# scr_precharge.net
KiCad netlist of a schematic drawn in EAGLE
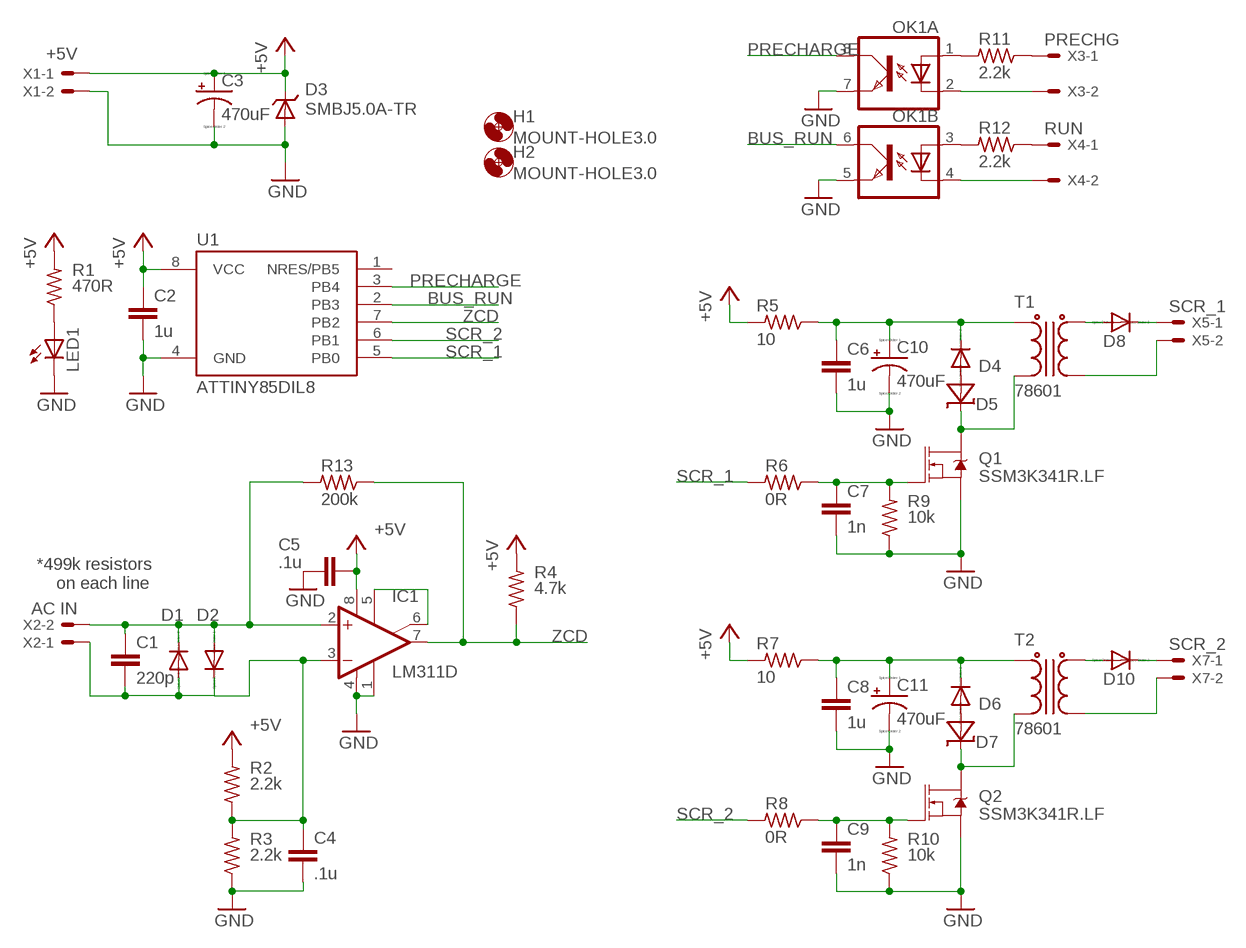
[diagram p0: schematic, sheet 1]

(export (version "E")
  (design (tool "Eeschema 10.0.6"))
  (components
    (comp (ref "C1")
      (value "220p")
      (footprint "eagle-import:C0805")
      (libsource (lib "eagle-import") (part "C-EUC0805"))
    )
    (comp (ref "C2")
      (value "1u")
      (footprint "eagle-import:C0805")
      (libsource (lib "eagle-import") (part "C-EUC0805"))
    )
    (comp (ref "C3")
      (value "470uF")
      (footprint "eagle-import:E3,5-8")
      (libsource (lib "eagle-import") (part "CPOL-USE3.5-8"))
    )
    (comp (ref "C4")
      (value ".1u")
      (footprint "eagle-import:C0805")
      (libsource (lib "eagle-import") (part "C-EUC0805"))
    )
    (comp (ref "C5")
      (value ".1u")
      (footprint "eagle-import:C0805")
      (libsource (lib "eagle-import") (part "C-EUC0805"))
    )
    (comp (ref "C6")
      (value "1u")
      (footprint "eagle-import:C0805")
      (libsource (lib "eagle-import") (part "C-EUC0805"))
    )
    (comp (ref "C7")
      (value "1n")
      (footprint "eagle-import:C0805")
      (libsource (lib "eagle-import") (part "C-EUC0805"))
    )
    (comp (ref "C8")
      (value "1u")
      (footprint "eagle-import:C0805")
      (libsource (lib "eagle-import") (part "C-EUC0805"))
    )
    (comp (ref "C9")
      (value "1n")
      (footprint "eagle-import:C0805")
      (libsource (lib "eagle-import") (part "C-EUC0805"))
    )
    (comp (ref "C10")
      (value "470uF")
      (footprint "eagle-import:E3,5-8")
      (libsource (lib "eagle-import") (part "CPOL-USE3.5-8"))
    )
    (comp (ref "C11")
      (value "470uF")
      (footprint "eagle-import:E3,5-8")
      (libsource (lib "eagle-import") (part "CPOL-USE3.5-8"))
    )
    (comp (ref "D1")
      (value "1N4148MICROMELF")
      (footprint "eagle-import:MICROMELF-W")
      (libsource (lib "eagle-import") (part "1N4148MICROMELF"))
    )
    (comp (ref "D2")
      (value "1N4148MICROMELF")
      (footprint "eagle-import:MICROMELF-W")
      (libsource (lib "eagle-import") (part "1N4148MICROMELF"))
    )
    (comp (ref "D3")
      (value "SMBJ5.0A-TR")
      (footprint "eagle-import:DO214AA")
      (libsource (lib "eagle-import") (part "SMBJ5.0A-TR"))
    )
    (comp (ref "D4")
      (value "1N4148MICROMELF")
      (footprint "eagle-import:MICROMELF-W")
      (libsource (lib "eagle-import") (part "1N4148MICROMELF"))
    )
    (comp (ref "D5")
      (value "SMAZ12-TP")
      (footprint "eagle-import:DO-214AC")
      (libsource (lib "eagle-import") (part "SMAZ12-TP"))
    )
    (comp (ref "D6")
      (value "1N4148MICROMELF")
      (footprint "eagle-import:MICROMELF-W")
      (libsource (lib "eagle-import") (part "1N4148MICROMELF"))
    )
    (comp (ref "D7")
      (value "SMAZ12-TP")
      (footprint "eagle-import:DO-214AC")
      (libsource (lib "eagle-import") (part "SMAZ12-TP"))
    )
    (comp (ref "D8")
      (value "1N4148MICROMELF")
      (footprint "eagle-import:MICROMELF-W")
      (libsource (lib "eagle-import") (part "1N4148MICROMELF"))
    )
    (comp (ref "D10")
      (value "1N4148MICROMELF")
      (footprint "eagle-import:MICROMELF-W")
      (libsource (lib "eagle-import") (part "1N4148MICROMELF"))
    )
    (comp (ref "H1")
      (value "MOUNT-HOLE3.0")
      (footprint "eagle-import:3,0")
      (libsource (lib "eagle-import") (part "MOUNT-HOLE3.0"))
    )
    (comp (ref "H2")
      (value "MOUNT-HOLE3.0")
      (footprint "eagle-import:3,0")
      (libsource (lib "eagle-import") (part "MOUNT-HOLE3.0"))
    )
    (comp (ref "IC1")
      (value "LM311D")
      (footprint "eagle-import:SO08")
      (libsource (lib "eagle-import") (part "LM311D"))
    )
    (comp (ref "LED1")
      (value "LEDCHIP-LED0805")
      (footprint "eagle-import:CHIP-LED0805")
      (libsource (lib "eagle-import") (part "LEDCHIP-LED0805"))
    )
    (comp (ref "OK1")
      (value "ILD621")
      (footprint "eagle-import:DIL08")
      (fields (field (name "MF") "VISHAY/TELEFUNKEN"))
      (libsource (lib "eagle-import") (part "ILD621"))
    )
    (comp (ref "Q1")
      (value "SSM3K341R.LF")
      (footprint "eagle-import:SOT23-3")
      (libsource (lib "eagle-import") (part "MOSFET-NCH-AO3404A"))
    )
    (comp (ref "Q2")
      (value "SSM3K341R.LF")
      (footprint "eagle-import:SOT23-3")
      (libsource (lib "eagle-import") (part "MOSFET-NCH-AO3404A"))
    )
    (comp (ref "R1")
      (value "470R")
      (footprint "eagle-import:R0805")
      (libsource (lib "eagle-import") (part "R-US_R0805"))
    )
    (comp (ref "R2")
      (value "2.2k")
      (footprint "eagle-import:R0805")
      (libsource (lib "eagle-import") (part "R-US_R0805"))
    )
    (comp (ref "R3")
      (value "2.2k")
      (footprint "eagle-import:R0805")
      (libsource (lib "eagle-import") (part "R-US_R0805"))
    )
    (comp (ref "R4")
      (value "4.7k")
      (footprint "eagle-import:R0805")
      (libsource (lib "eagle-import") (part "R-US_R0805"))
    )
    (comp (ref "R5")
      (value "10")
      (footprint "eagle-import:R2010")
      (libsource (lib "eagle-import") (part "R-US_R2010"))
    )
    (comp (ref "R6")
      (value "0R")
      (footprint "eagle-import:R0805")
      (libsource (lib "eagle-import") (part "R-US_R0805"))
    )
    (comp (ref "R7")
      (value "10")
      (footprint "eagle-import:R2010")
      (libsource (lib "eagle-import") (part "R-US_R2010"))
    )
    (comp (ref "R8")
      (value "0R")
      (footprint "eagle-import:R0805")
      (libsource (lib "eagle-import") (part "R-US_R0805"))
    )
    (comp (ref "R9")
      (value "10k")
      (footprint "eagle-import:R0805")
      (libsource (lib "eagle-import") (part "R-US_R0805"))
    )
    (comp (ref "R10")
      (value "10k")
      (footprint "eagle-import:R0805")
      (libsource (lib "eagle-import") (part "R-US_R0805"))
    )
    (comp (ref "R11")
      (value "2.2k")
      (footprint "eagle-import:R0805")
      (libsource (lib "eagle-import") (part "R-US_R0805"))
    )
    (comp (ref "R12")
      (value "2.2k")
      (footprint "eagle-import:R0805")
      (libsource (lib "eagle-import") (part "R-US_R0805"))
    )
    (comp (ref "R13")
      (value "200k")
      (footprint "eagle-import:R0805")
      (libsource (lib "eagle-import") (part "R-US_R0805"))
    )
    (comp (ref "T1")
      (value "78601")
      (footprint "eagle-import:J-STD-020D")
      (libsource (lib "eagle-import") (part "78601"))
    )
    (comp (ref "T2")
      (value "78601")
      (footprint "eagle-import:J-STD-020D")
      (libsource (lib "eagle-import") (part "78601"))
    )
    (comp (ref "U1")
      (value "ATTINY85DIL8")
      (footprint "eagle-import:DIL8")
      (libsource (lib "eagle-import") (part "ATTINY85DIL8"))
    )
    (comp (ref "X1")
      (value "+5V")
      (footprint "eagle-import:22-23-2021")
      (fields (field (name "MF") "MOLEX") (field (name "MPN") "22-23-2021"))
      (libsource (lib "eagle-import") (part "22-23-2021"))
    )
    (comp (ref "X2")
      (value "AC IN")
      (footprint "eagle-import:22-23-2021")
      (fields (field (name "MF") "MOLEX") (field (name "MPN") "22-23-2021"))
      (libsource (lib "eagle-import") (part "22-23-2021"))
    )
    (comp (ref "X3")
      (value "PRECHG")
      (footprint "eagle-import:22-23-2021")
      (fields (field (name "MF") "MOLEX") (field (name "MPN") "22-23-2021"))
      (libsource (lib "eagle-import") (part "22-23-2021"))
    )
    (comp (ref "X4")
      (value "RUN")
      (footprint "eagle-import:22-23-2021")
      (fields (field (name "MF") "MOLEX") (field (name "MPN") "22-23-2021"))
      (libsource (lib "eagle-import") (part "22-23-2021"))
    )
    (comp (ref "X5")
      (value "SCR_1")
      (footprint "eagle-import:22-23-2021")
      (fields (field (name "MF") "MOLEX") (field (name "MPN") "22-23-2021"))
      (libsource (lib "eagle-import") (part "22-23-2021"))
    )
    (comp (ref "X7")
      (value "SCR_2")
      (footprint "eagle-import:22-23-2021")
      (fields (field (name "MF") "MOLEX") (field (name "MPN") "22-23-2021"))
      (libsource (lib "eagle-import") (part "22-23-2021"))
    )
  )
  (nets
    (net (code "1") (name "+5V") (class "Default")
      (node (ref "C2") (pin "1") (pinfunction "1_1") (pintype "passive"))
      (node (ref "C3") (pin "+") (pinfunction "+_+") (pintype "passive"))
      (node (ref "C5") (pin "2") (pinfunction "2_2") (pintype "passive"))
      (node (ref "D3") (pin "C") (pinfunction "C_C") (pintype "passive"))
      (node (ref "IC1") (pin "8") (pinfunction "V+_8") (pintype "power_in"))
      (node (ref "R1") (pin "2") (pinfunction "2_2") (pintype "passive"))
      (node (ref "R2") (pin "2") (pinfunction "2_2") (pintype "passive"))
      (node (ref "R4") (pin "2") (pinfunction "2_2") (pintype "passive"))
      (node (ref "R5") (pin "2") (pinfunction "2_2") (pintype "passive"))
      (node (ref "R7") (pin "2") (pinfunction "2_2") (pintype "passive"))
      (node (ref "U1") (pin "8") (pinfunction "VCC_8") (pintype "power_in"))
      (node (ref "X1") (pin "1") (pinfunction "S_1") (pintype "passive"))
    )
    (net (code "2") (name "/BUS_RUN") (class "Default")
      (node (ref "OK1") (pin "6") (pinfunction "COL_6") (pintype "passive"))
      (node (ref "U1") (pin "2") (pinfunction "PB3_2") (pintype "bidirectional"))
    )
    (net (code "3") (name "/PRECHARGE") (class "Default")
      (node (ref "OK1") (pin "8") (pinfunction "COL_8") (pintype "passive"))
      (node (ref "U1") (pin "3") (pinfunction "PB4_3") (pintype "bidirectional"))
    )
    (net (code "4") (name "/SCR_1") (class "Default")
      (node (ref "R6") (pin "2") (pinfunction "2_2") (pintype "passive"))
      (node (ref "U1") (pin "5") (pinfunction "PB0_5") (pintype "bidirectional"))
    )
    (net (code "5") (name "/SCR_2") (class "Default")
      (node (ref "R8") (pin "2") (pinfunction "2_2") (pintype "passive"))
      (node (ref "U1") (pin "6") (pinfunction "PB1_6") (pintype "bidirectional"))
    )
    (net (code "6") (name "/ZCD") (class "Default")
      (node (ref "IC1") (pin "7") (pinfunction "OUT_7") (pintype "output"))
      (node (ref "R13") (pin "1") (pinfunction "1_1") (pintype "passive"))
      (node (ref "R4") (pin "1") (pinfunction "1_1") (pintype "passive"))
      (node (ref "U1") (pin "7") (pinfunction "PB2_7") (pintype "bidirectional"))
    )
    (net (code "7") (name "GND") (class "Default")
      (node (ref "C10") (pin "-") (pinfunction "-_-") (pintype "passive"))
      (node (ref "C11") (pin "-") (pinfunction "-_-") (pintype "passive"))
      (node (ref "C2") (pin "2") (pinfunction "2_2") (pintype "passive"))
      (node (ref "C3") (pin "-") (pinfunction "-_-") (pintype "passive"))
      (node (ref "C4") (pin "2") (pinfunction "2_2") (pintype "passive"))
      (node (ref "C5") (pin "1") (pinfunction "1_1") (pintype "passive"))
      (node (ref "C6") (pin "2") (pinfunction "2_2") (pintype "passive"))
      (node (ref "C7") (pin "2") (pinfunction "2_2") (pintype "passive"))
      (node (ref "C8") (pin "2") (pinfunction "2_2") (pintype "passive"))
      (node (ref "C9") (pin "2") (pinfunction "2_2") (pintype "passive"))
      (node (ref "D3") (pin "A") (pinfunction "A_A") (pintype "passive"))
      (node (ref "IC1") (pin "1") (pinfunction "GND_1") (pintype "passive"))
      (node (ref "IC1") (pin "4") (pinfunction "V-_4") (pintype "power_in"))
      (node (ref "LED1") (pin "C") (pinfunction "C_C") (pintype "passive"))
      (node (ref "OK1") (pin "5") (pinfunction "EMIT_5") (pintype "passive"))
      (node (ref "OK1") (pin "7") (pinfunction "EMIT_7") (pintype "passive"))
      (node (ref "Q1") (pin "2") (pinfunction "S_2") (pintype "bidirectional"))
      (node (ref "Q2") (pin "2") (pinfunction "S_2") (pintype "bidirectional"))
      (node (ref "R10") (pin "1") (pinfunction "1_1") (pintype "passive"))
      (node (ref "R3") (pin "1") (pinfunction "1_1") (pintype "passive"))
      (node (ref "R9") (pin "1") (pinfunction "1_1") (pintype "passive"))
      (node (ref "U1") (pin "4") (pinfunction "GND_4") (pintype "power_in"))
      (node (ref "X1") (pin "2") (pinfunction "S_2") (pintype "passive"))
    )
    (net (code "8") (name "Net-(C10-Pad+)") (class "Default")
      (node (ref "C10") (pin "+") (pinfunction "+_+") (pintype "passive"))
      (node (ref "C6") (pin "1") (pinfunction "1_1") (pintype "passive"))
      (node (ref "D4") (pin "C") (pinfunction "C_C") (pintype "passive"))
      (node (ref "R5") (pin "1") (pinfunction "1_1") (pintype "passive"))
      (node (ref "T1") (pin "P$1") (pinfunction "P$1_P$1") (pintype "bidirectional"))
    )
    (net (code "9") (name "Net-(C11-Pad+)") (class "Default")
      (node (ref "C11") (pin "+") (pinfunction "+_+") (pintype "passive"))
      (node (ref "C8") (pin "1") (pinfunction "1_1") (pintype "passive"))
      (node (ref "D6") (pin "C") (pinfunction "C_C") (pintype "passive"))
      (node (ref "R7") (pin "1") (pinfunction "1_1") (pintype "passive"))
      (node (ref "T2") (pin "P$1") (pinfunction "P$1_P$1") (pintype "bidirectional"))
    )
    (net (code "10") (name "Net-(D4-PadA)") (class "Default")
      (node (ref "D4") (pin "A") (pinfunction "A_A") (pintype "passive"))
      (node (ref "D5") (pin "A") (pinfunction "A_A") (pintype "passive"))
    )
    (net (code "11") (name "Net-(D6-PadA)") (class "Default")
      (node (ref "D6") (pin "A") (pinfunction "A_A") (pintype "passive"))
      (node (ref "D7") (pin "A") (pinfunction "A_A") (pintype "passive"))
    )
    (net (code "12") (name "Net-(D8-PadA)") (class "Default")
      (node (ref "D8") (pin "A") (pinfunction "A_A") (pintype "passive"))
      (node (ref "T1") (pin "P$6") (pinfunction "P$6_P$6") (pintype "bidirectional"))
    )
    (net (code "13") (name "Net-(D10-PadA)") (class "Default")
      (node (ref "D10") (pin "A") (pinfunction "A_A") (pintype "passive"))
      (node (ref "T2") (pin "P$6") (pinfunction "P$6_P$6") (pintype "bidirectional"))
    )
    (net (code "14") (name "Net-(IC1-+IN)") (class "Default")
      (node (ref "C1") (pin "1") (pinfunction "1_1") (pintype "passive"))
      (node (ref "D1") (pin "C") (pinfunction "C_C") (pintype "passive"))
      (node (ref "D2") (pin "A") (pinfunction "A_A") (pintype "passive"))
      (node (ref "IC1") (pin "2") (pinfunction "+IN_2") (pintype "input"))
      (node (ref "R13") (pin "2") (pinfunction "2_2") (pintype "passive"))
      (node (ref "X2") (pin "2") (pinfunction "S_2") (pintype "passive"))
    )
    (net (code "15") (name "Net-(IC1--IN)") (class "Default")
      (node (ref "C1") (pin "2") (pinfunction "2_2") (pintype "passive"))
      (node (ref "C4") (pin "1") (pinfunction "1_1") (pintype "passive"))
      (node (ref "D1") (pin "A") (pinfunction "A_A") (pintype "passive"))
      (node (ref "D2") (pin "C") (pinfunction "C_C") (pintype "passive"))
      (node (ref "IC1") (pin "3") (pinfunction "-IN_3") (pintype "input"))
      (node (ref "R2") (pin "1") (pinfunction "1_1") (pintype "passive"))
      (node (ref "R3") (pin "2") (pinfunction "2_2") (pintype "passive"))
      (node (ref "X2") (pin "1") (pinfunction "S_1") (pintype "passive"))
    )
    (net (code "16") (name "Net-(IC1-ON)") (class "Default")
      (node (ref "IC1") (pin "5") (pinfunction "ON_5") (pintype "passive"))
      (node (ref "IC1") (pin "6") (pinfunction "ON/STR_6") (pintype "passive"))
    )
    (net (code "17") (name "Net-(LED1-PadA)") (class "Default")
      (node (ref "LED1") (pin "A") (pinfunction "A_A") (pintype "passive"))
      (node (ref "R1") (pin "1") (pinfunction "1_1") (pintype "passive"))
    )
    (net (code "18") (name "Net-(OK1A-A)") (class "Default")
      (node (ref "OK1") (pin "1") (pinfunction "A_1") (pintype "passive"))
      (node (ref "R11") (pin "2") (pinfunction "2_2") (pintype "passive"))
    )
    (net (code "19") (name "Net-(OK1A-C)") (class "Default")
      (node (ref "OK1") (pin "2") (pinfunction "C_2") (pintype "passive"))
      (node (ref "X3") (pin "2") (pinfunction "S_2") (pintype "passive"))
    )
    (net (code "20") (name "Net-(OK1B-A)") (class "Default")
      (node (ref "OK1") (pin "3") (pinfunction "A_3") (pintype "passive"))
      (node (ref "R12") (pin "2") (pinfunction "2_2") (pintype "passive"))
    )
    (net (code "21") (name "Net-(OK1B-C)") (class "Default")
      (node (ref "OK1") (pin "4") (pinfunction "C_4") (pintype "passive"))
      (node (ref "X4") (pin "2") (pinfunction "S_2") (pintype "passive"))
    )
    (net (code "22") (name "Net-(Q1-D)") (class "Default")
      (node (ref "D5") (pin "C") (pinfunction "C_C") (pintype "passive"))
      (node (ref "Q1") (pin "3") (pinfunction "D_3") (pintype "bidirectional"))
      (node (ref "T1") (pin "P$3") (pinfunction "P$3_P$3") (pintype "bidirectional"))
    )
    (net (code "23") (name "Net-(Q1-G)") (class "Default")
      (node (ref "C7") (pin "1") (pinfunction "1_1") (pintype "passive"))
      (node (ref "Q1") (pin "1") (pinfunction "G_1") (pintype "bidirectional"))
      (node (ref "R6") (pin "1") (pinfunction "1_1") (pintype "passive"))
      (node (ref "R9") (pin "2") (pinfunction "2_2") (pintype "passive"))
    )
    (net (code "24") (name "Net-(Q2-D)") (class "Default")
      (node (ref "D7") (pin "C") (pinfunction "C_C") (pintype "passive"))
      (node (ref "Q2") (pin "3") (pinfunction "D_3") (pintype "bidirectional"))
      (node (ref "T2") (pin "P$3") (pinfunction "P$3_P$3") (pintype "bidirectional"))
    )
    (net (code "25") (name "Net-(Q2-G)") (class "Default")
      (node (ref "C9") (pin "1") (pinfunction "1_1") (pintype "passive"))
      (node (ref "Q2") (pin "1") (pinfunction "G_1") (pintype "bidirectional"))
      (node (ref "R10") (pin "2") (pinfunction "2_2") (pintype "passive"))
      (node (ref "R8") (pin "1") (pinfunction "1_1") (pintype "passive"))
    )
    (net (code "26") (name "Net-(X3A-S)") (class "Default")
      (node (ref "R11") (pin "1") (pinfunction "1_1") (pintype "passive"))
      (node (ref "X3") (pin "1") (pinfunction "S_1") (pintype "passive"))
    )
    (net (code "27") (name "Net-(X4A-S)") (class "Default")
      (node (ref "R12") (pin "1") (pinfunction "1_1") (pintype "passive"))
      (node (ref "X4") (pin "1") (pinfunction "S_1") (pintype "passive"))
    )
    (net (code "28") (name "Net-(X5A-S)") (class "Default")
      (node (ref "D8") (pin "C") (pinfunction "C_C") (pintype "passive"))
      (node (ref "X5") (pin "1") (pinfunction "S_1") (pintype "passive"))
    )
    (net (code "29") (name "Net-(X5B-S)") (class "Default")
      (node (ref "T1") (pin "P$4") (pinfunction "P$4_P$4") (pintype "bidirectional"))
      (node (ref "X5") (pin "2") (pinfunction "S_2") (pintype "passive"))
    )
    (net (code "30") (name "Net-(X7A-S)") (class "Default")
      (node (ref "D10") (pin "C") (pinfunction "C_C") (pintype "passive"))
      (node (ref "X7") (pin "1") (pinfunction "S_1") (pintype "passive"))
    )
    (net (code "31") (name "Net-(X7B-S)") (class "Default")
      (node (ref "T2") (pin "P$4") (pinfunction "P$4_P$4") (pintype "bidirectional"))
      (node (ref "X7") (pin "2") (pinfunction "S_2") (pintype "passive"))
    )
    (net (code "32") (name "unconnected-(U1-NRES{slash}PB5-Pad1)") (class "Default")
      (node (ref "U1") (pin "1") (pinfunction "NRES/PB5_1") (pintype "bidirectional"))
    )
  )
)
